# BME280_I2C.net
KiCad netlist of a schematic drawn in Altium Designer
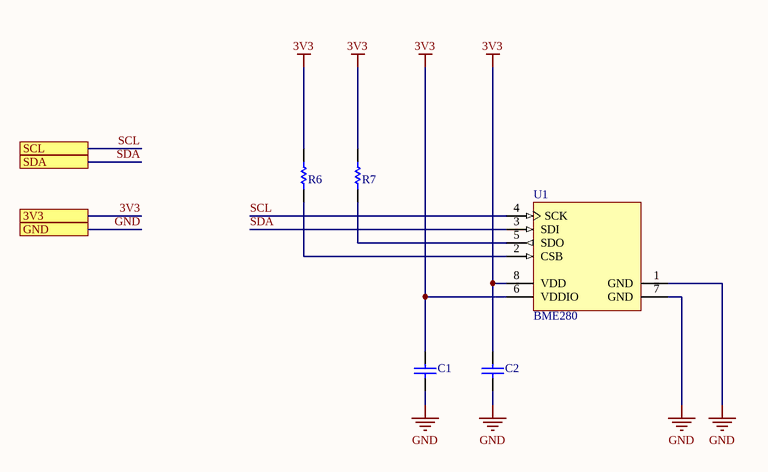
[diagram p0: BME280_I2C.SchDoc]

(export (version "E")
  (design (tool "Eeschema 10.0.6"))
  (components
    (comp (ref "C1")
      (value "C0805C104J5RAC7800")
      (footprint "CAPC2013X145X50NL20T25")
      (description "0.1µF ±5% 50V Ceramic Capacitor X7R 0805 (2012 Metric)")
      (fields (field (name "MANUFACTURER") "Kemet"))
      (libsource (lib "Altium Content Vault") (part "CAP"))
    )
    (comp (ref "C2")
      (value "C0805C104J5RAC7800")
      (footprint "CAPC2013X145X50NL20T25")
      (description "0.1µF ±5% 50V Ceramic Capacitor X7R 0805 (2012 Metric)")
      (fields (field (name "MANUFACTURER") "Kemet"))
      (libsource (lib "Altium Content Vault") (part "CAP"))
    )
    (comp (ref "R6")
      (value "RC0805JR-074K7L")
      (footprint "RESC2013X60X30NL20T20")
      (description "4.7 kOhms ±5% 0.125W, 1/8W Chip Resistor 0805 (2012 Metric) Moisture Resistant Thick Film")
      (fields (field (name "MANUFACTURER") "Yageo"))
      (libsource (lib "LIB_FIT") (part "RC0805JR-074K7L"))
    )
    (comp (ref "R7")
      (value "RC0805JR-074K7L")
      (footprint "RESC2013X60X30NL20T20")
      (description "4.7 kOhms ±5% 0.125W, 1/8W Chip Resistor 0805 (2012 Metric) Moisture Resistant Thick Film")
      (fields (field (name "MANUFACTURER") "Yageo"))
      (libsource (lib "LIB_FIT") (part "RC0805JR-074K7L"))
    )
    (comp (ref "U1")
      (value "BME280")
      (footprint "BOSC-BME280-8_V")
      (fields (field (name "MANUFACTURER") "Bosch Sensortec"))
      (libsource (lib "Altium Content Vault") (part "BOSC-BME280-8"))
    )
  )
  (nets
    (net (code "1") (name "/SCL") (class "Default")
      (node (ref "U1") (pin "4") (pinfunction "SCK_4") (pintype "input"))
    )
    (net (code "2") (name "/SDA") (class "Default")
      (node (ref "U1") (pin "3") (pinfunction "SDI_3") (pintype "input"))
    )
    (net (code "3") (name "3V3") (class "Default")
      (node (ref "C1") (pin "2") (pinfunction "2_2") (pintype "passive"))
      (node (ref "C2") (pin "2") (pinfunction "2_2") (pintype "passive"))
      (node (ref "R6") (pin "2") (pinfunction "2_2") (pintype "passive"))
      (node (ref "R7") (pin "2") (pinfunction "2_2") (pintype "passive"))
      (node (ref "U1") (pin "6") (pinfunction "VDDIO_6") (pintype "power_in"))
      (node (ref "U1") (pin "8") (pinfunction "VDD_8") (pintype "power_in"))
    )
    (net (code "4") (name "GND") (class "Default")
      (node (ref "C1") (pin "1") (pinfunction "1_1") (pintype "passive"))
      (node (ref "C2") (pin "1") (pinfunction "1_1") (pintype "passive"))
      (node (ref "U1") (pin "1") (pinfunction "GND_1") (pintype "power_in"))
      (node (ref "U1") (pin "7") (pinfunction "GND_7") (pintype "power_in"))
    )
    (net (code "5") (name "Net-(U1-CSB)") (class "Default")
      (node (ref "R6") (pin "1") (pinfunction "1_1") (pintype "passive"))
      (node (ref "U1") (pin "2") (pinfunction "CSB_2") (pintype "input"))
    )
    (net (code "6") (name "Net-(U1-SDO)") (class "Default")
      (node (ref "R7") (pin "1") (pinfunction "1_1") (pintype "passive"))
      (node (ref "U1") (pin "5") (pinfunction "SDO_5") (pintype "output"))
    )
  )
)
